# 6_CH340C.net
KiCad netlist of a schematic drawn in Altium Designer
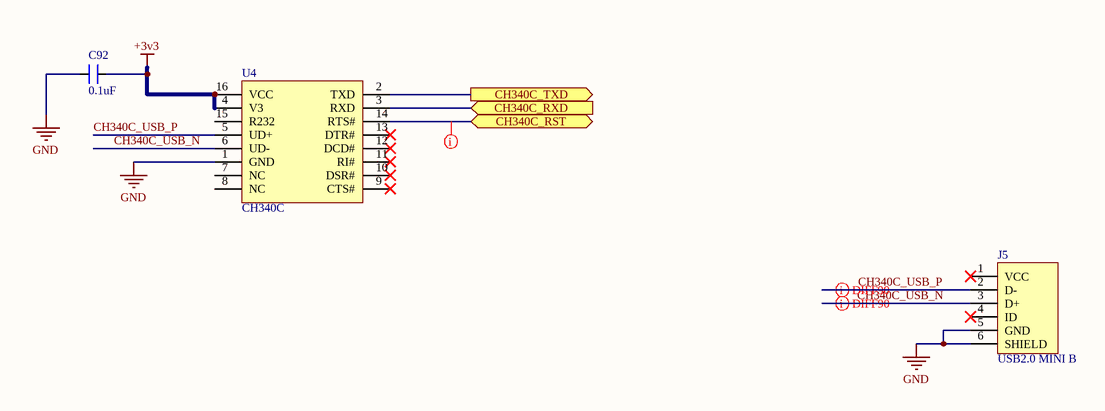
[diagram p0: [6]CH340C.SchDoc]

(export (version "E")
  (design (tool "Eeschema 10.0.6"))
  (components
    (comp (ref "C92")
      (value "0.1uF")
      (footprint "CAP_0805")
      (description "0.1µF ±5% 50V Ceramic Capacitor X7R 0805 (2012 Metric)")
      (fields
        (field (name "MANUFACTURER") "AVX Corporation")
        (field (name "MANUFACTURER PART NUMBER") "08055C104JAT4A")
      )
      (libsource (lib "ESTEEMPCBLIB") (part "CAP_0.1uF-50V-5%-0805"))
    )
    (comp (ref "J5")
      (value "USB2.0 MINI B")
      (footprint "CON_690-005-299-043")
      (description "USB - mini B USB 2.0 Receptacle Connector 5 Position Surface Mount, Right Angle")
      (fields
        (field (name "MANUFACTURER") "EDAC")
        (field (name "MANUFACTURER PART NUMBER") "690-005-299-043")
      )
      (libsource (lib "ESTEEMPCBLIB") (part "CON_USB2.0-MINIB-SMD"))
    )
    (comp (ref "U4")
      (value "CH340C")
      (footprint "SOIC16_50_284_25X90_SMT")
      (description "USB Bridge, USB to UART USB 2.0 UART Interface")
      (fields (field (name "MANUFACTURER") "Olimex"))
      (libsource (lib "ESTEEMPCBLIB") (part "IC_CH340C"))
    )
  )
  (nets
    (net (code "1") (name "+3v3") (class "Default")
      (node (ref "C92") (pin "2") (pinfunction "2_2") (pintype "passive"))
      (node (ref "U4") (pin "16") (pinfunction "VCC_16") (pintype "passive"))
      (node (ref "U4") (pin "4") (pinfunction "V3_4") (pintype "passive"))
    )
    (net (code "2") (name "/CH340C_RST") (class "Default")
      (node (ref "U4") (pin "14") (pinfunction "RTS#_14") (pintype "passive"))
    )
    (net (code "3") (name "/CH340C_RXD") (class "Default")
      (node (ref "U4") (pin "3") (pinfunction "RXD_3") (pintype "passive"))
    )
    (net (code "4") (name "/CH340C_TXD") (class "Default")
      (node (ref "U4") (pin "2") (pinfunction "TXD_2") (pintype "passive"))
    )
    (net (code "5") (name "/CH340C_USB_N") (class "Default")
      (node (ref "J5") (pin "3") (pinfunction "D+_3") (pintype "passive"))
      (node (ref "U4") (pin "6") (pinfunction "UD-_6") (pintype "passive"))
    )
    (net (code "6") (name "/CH340C_USB_P") (class "Default")
      (node (ref "J5") (pin "2") (pinfunction "D-_2") (pintype "passive"))
      (node (ref "U4") (pin "5") (pinfunction "UD+_5") (pintype "passive"))
    )
    (net (code "7") (name "GND") (class "Default")
      (node (ref "C92") (pin "1") (pinfunction "1_1") (pintype "passive"))
      (node (ref "J5") (pin "5") (pinfunction "GND_5") (pintype "passive"))
      (node (ref "J5") (pin "6") (pinfunction "SHIELD_6") (pintype "passive"))
      (node (ref "U4") (pin "1") (pinfunction "GND_1") (pintype "passive"))
    )
    (net (code "8") (name "unconnected-(J5-ID-Pad4)") (class "Default")
      (node (ref "J5") (pin "4") (pinfunction "ID_4") (pintype "passive+no_connect"))
    )
    (net (code "9") (name "unconnected-(J5-VCC-Pad1)") (class "Default")
      (node (ref "J5") (pin "1") (pinfunction "VCC_1") (pintype "passive+no_connect"))
    )
    (net (code "10") (name "unconnected-(U4-CTS#-Pad9)") (class "Default")
      (node (ref "U4") (pin "9") (pinfunction "CTS#_9") (pintype "passive+no_connect"))
    )
    (net (code "11") (name "unconnected-(U4-DCD#-Pad12)") (class "Default")
      (node (ref "U4") (pin "12") (pinfunction "DCD#_12") (pintype "passive+no_connect"))
    )
    (net (code "12") (name "unconnected-(U4-DSR#-Pad10)") (class "Default")
      (node (ref "U4") (pin "10") (pinfunction "DSR#_10") (pintype "passive+no_connect"))
    )
    (net (code "13") (name "unconnected-(U4-DTR#-Pad13)") (class "Default")
      (node (ref "U4") (pin "13") (pinfunction "DTR#_13") (pintype "passive+no_connect"))
    )
    (net (code "14") (name "unconnected-(U4-NC-Pad7)") (class "Default")
      (node (ref "U4") (pin "7") (pinfunction "NC_7") (pintype "passive"))
    )
    (net (code "15") (name "unconnected-(U4-NC-Pad8)") (class "Default")
      (node (ref "U4") (pin "8") (pinfunction "NC_8") (pintype "passive"))
    )
    (net (code "16") (name "unconnected-(U4-R232-Pad15)") (class "Default")
      (node (ref "U4") (pin "15") (pinfunction "R232_15") (pintype "passive"))
    )
    (net (code "17") (name "unconnected-(U4-RI#-Pad11)") (class "Default")
      (node (ref "U4") (pin "11") (pinfunction "RI#_11") (pintype "passive+no_connect"))
    )
  )
)
